# lipo-charger.net
KiCad netlist of a schematic drawn in EAGLE
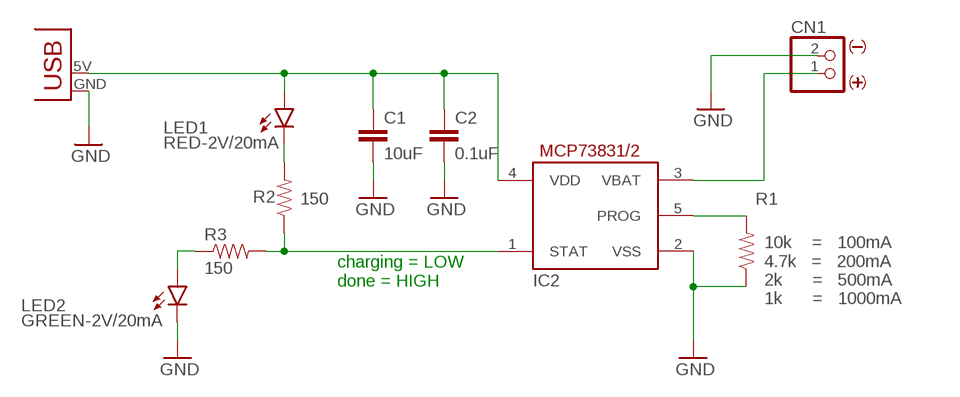
[diagram p0: schematic, sheet 1]

(export (version "E")
  (design (tool "Eeschema 10.0.6"))
  (components
    (comp (ref "C1")
      (value "10uF")
      (footprint "eagle-import:0805")
      (libsource (lib "eagle-import") (part "CAP-0805"))
    )
    (comp (ref "C2")
      (value "0.1uF")
      (footprint "eagle-import:0805")
      (libsource (lib "eagle-import") (part "CAP-0805"))
    )
    (comp (ref "CN1")
      (value "JST_2PIN_BATTERY-SMT-HORIZ")
      (footprint "eagle-import:JST-PH-2-SMT-RA")
      (libsource (lib "eagle-import") (part "JST_2PIN_BATTERY-SMT-HORIZ"))
    )
    (comp (ref "IC2")
      (value "LIPO_CHARGER/OT")
      (footprint "eagle-import:SOT23-5L")
      (libsource (lib "eagle-import") (part "LIPO_CHARGER/OT"))
    )
    (comp (ref "LED1")
      (value "RED-2V/20mA")
      (footprint "eagle-import:CHIP-LED0805")
      (libsource (lib "eagle-import") (part "LED-0805"))
    )
    (comp (ref "LED2")
      (value "GREEN-2V/20mA")
      (footprint "eagle-import:CHIP-LED0805")
      (libsource (lib "eagle-import") (part "LED-0805"))
    )
    (comp (ref "R1")
      (value "10k")
      (footprint "eagle-import:0805")
      (libsource (lib "eagle-import") (part "RESISTOR-0805"))
    )
    (comp (ref "R2")
      (value "150")
      (footprint "eagle-import:0805")
      (libsource (lib "eagle-import") (part "RESISTOR-0805"))
    )
    (comp (ref "R3")
      (value "150")
      (footprint "eagle-import:0805")
      (libsource (lib "eagle-import") (part "RESISTOR-0805"))
    )
    (comp (ref "U$2")
      (value "USB-PCB-POWER")
      (footprint "eagle-import:USB-A-PCB-POWER")
      (libsource (lib "eagle-import") (part "USB-PCB-POWER"))
    )
  )
  (nets
    (net (code "1") (name "GND") (class "Default")
      (node (ref "C1") (pin "2") (pinfunction "2_2") (pintype "passive"))
      (node (ref "C2") (pin "2") (pinfunction "2_2") (pintype "passive"))
      (node (ref "CN1") (pin "2") (pinfunction "1_2") (pintype "passive"))
      (node (ref "IC2") (pin "2") (pinfunction "VSS_2") (pintype "power_in"))
      (node (ref "LED2") (pin "C") (pinfunction "C_C") (pintype "passive"))
      (node (ref "R1") (pin "1") (pinfunction "1_1") (pintype "passive"))
      (node (ref "U$2") (pin "GND") (pinfunction "GND_GND") (pintype "bidirectional"))
    )
    (net (code "2") (name "Net-(CN1-2)") (class "Default")
      (node (ref "CN1") (pin "1") (pinfunction "2_1") (pintype "passive"))
      (node (ref "IC2") (pin "3") (pinfunction "VBAT_3") (pintype "bidirectional"))
    )
    (net (code "3") (name "Net-(IC2-PROG)") (class "Default")
      (node (ref "IC2") (pin "5") (pinfunction "PROG_5") (pintype "input"))
      (node (ref "R1") (pin "2") (pinfunction "2_2") (pintype "passive"))
    )
    (net (code "4") (name "Net-(IC2-STAT)") (class "Default")
      (node (ref "IC2") (pin "1") (pinfunction "STAT_1") (pintype "output"))
      (node (ref "R2") (pin "1") (pinfunction "1_1") (pintype "passive"))
      (node (ref "R3") (pin "2") (pinfunction "2_2") (pintype "passive"))
    )
    (net (code "5") (name "Net-(IC2-VDD)") (class "Default")
      (node (ref "C1") (pin "1") (pinfunction "1_1") (pintype "passive"))
      (node (ref "C2") (pin "1") (pinfunction "1_1") (pintype "passive"))
      (node (ref "IC2") (pin "4") (pinfunction "VDD_4") (pintype "power_in"))
      (node (ref "LED1") (pin "A") (pinfunction "A_A") (pintype "passive"))
      (node (ref "U$2") (pin "5V") (pinfunction "VBUS_5V") (pintype "bidirectional"))
    )
    (net (code "6") (name "Net-(LED1-PadC)") (class "Default")
      (node (ref "LED1") (pin "C") (pinfunction "C_C") (pintype "passive"))
      (node (ref "R2") (pin "2") (pinfunction "2_2") (pintype "passive"))
    )
    (net (code "7") (name "Net-(LED2-PadA)") (class "Default")
      (node (ref "LED2") (pin "A") (pinfunction "A_A") (pintype "passive"))
      (node (ref "R3") (pin "1") (pinfunction "1_1") (pintype "passive"))
    )
  )
)
